# controller.net
KiCad netlist of a schematic drawn in EAGLE
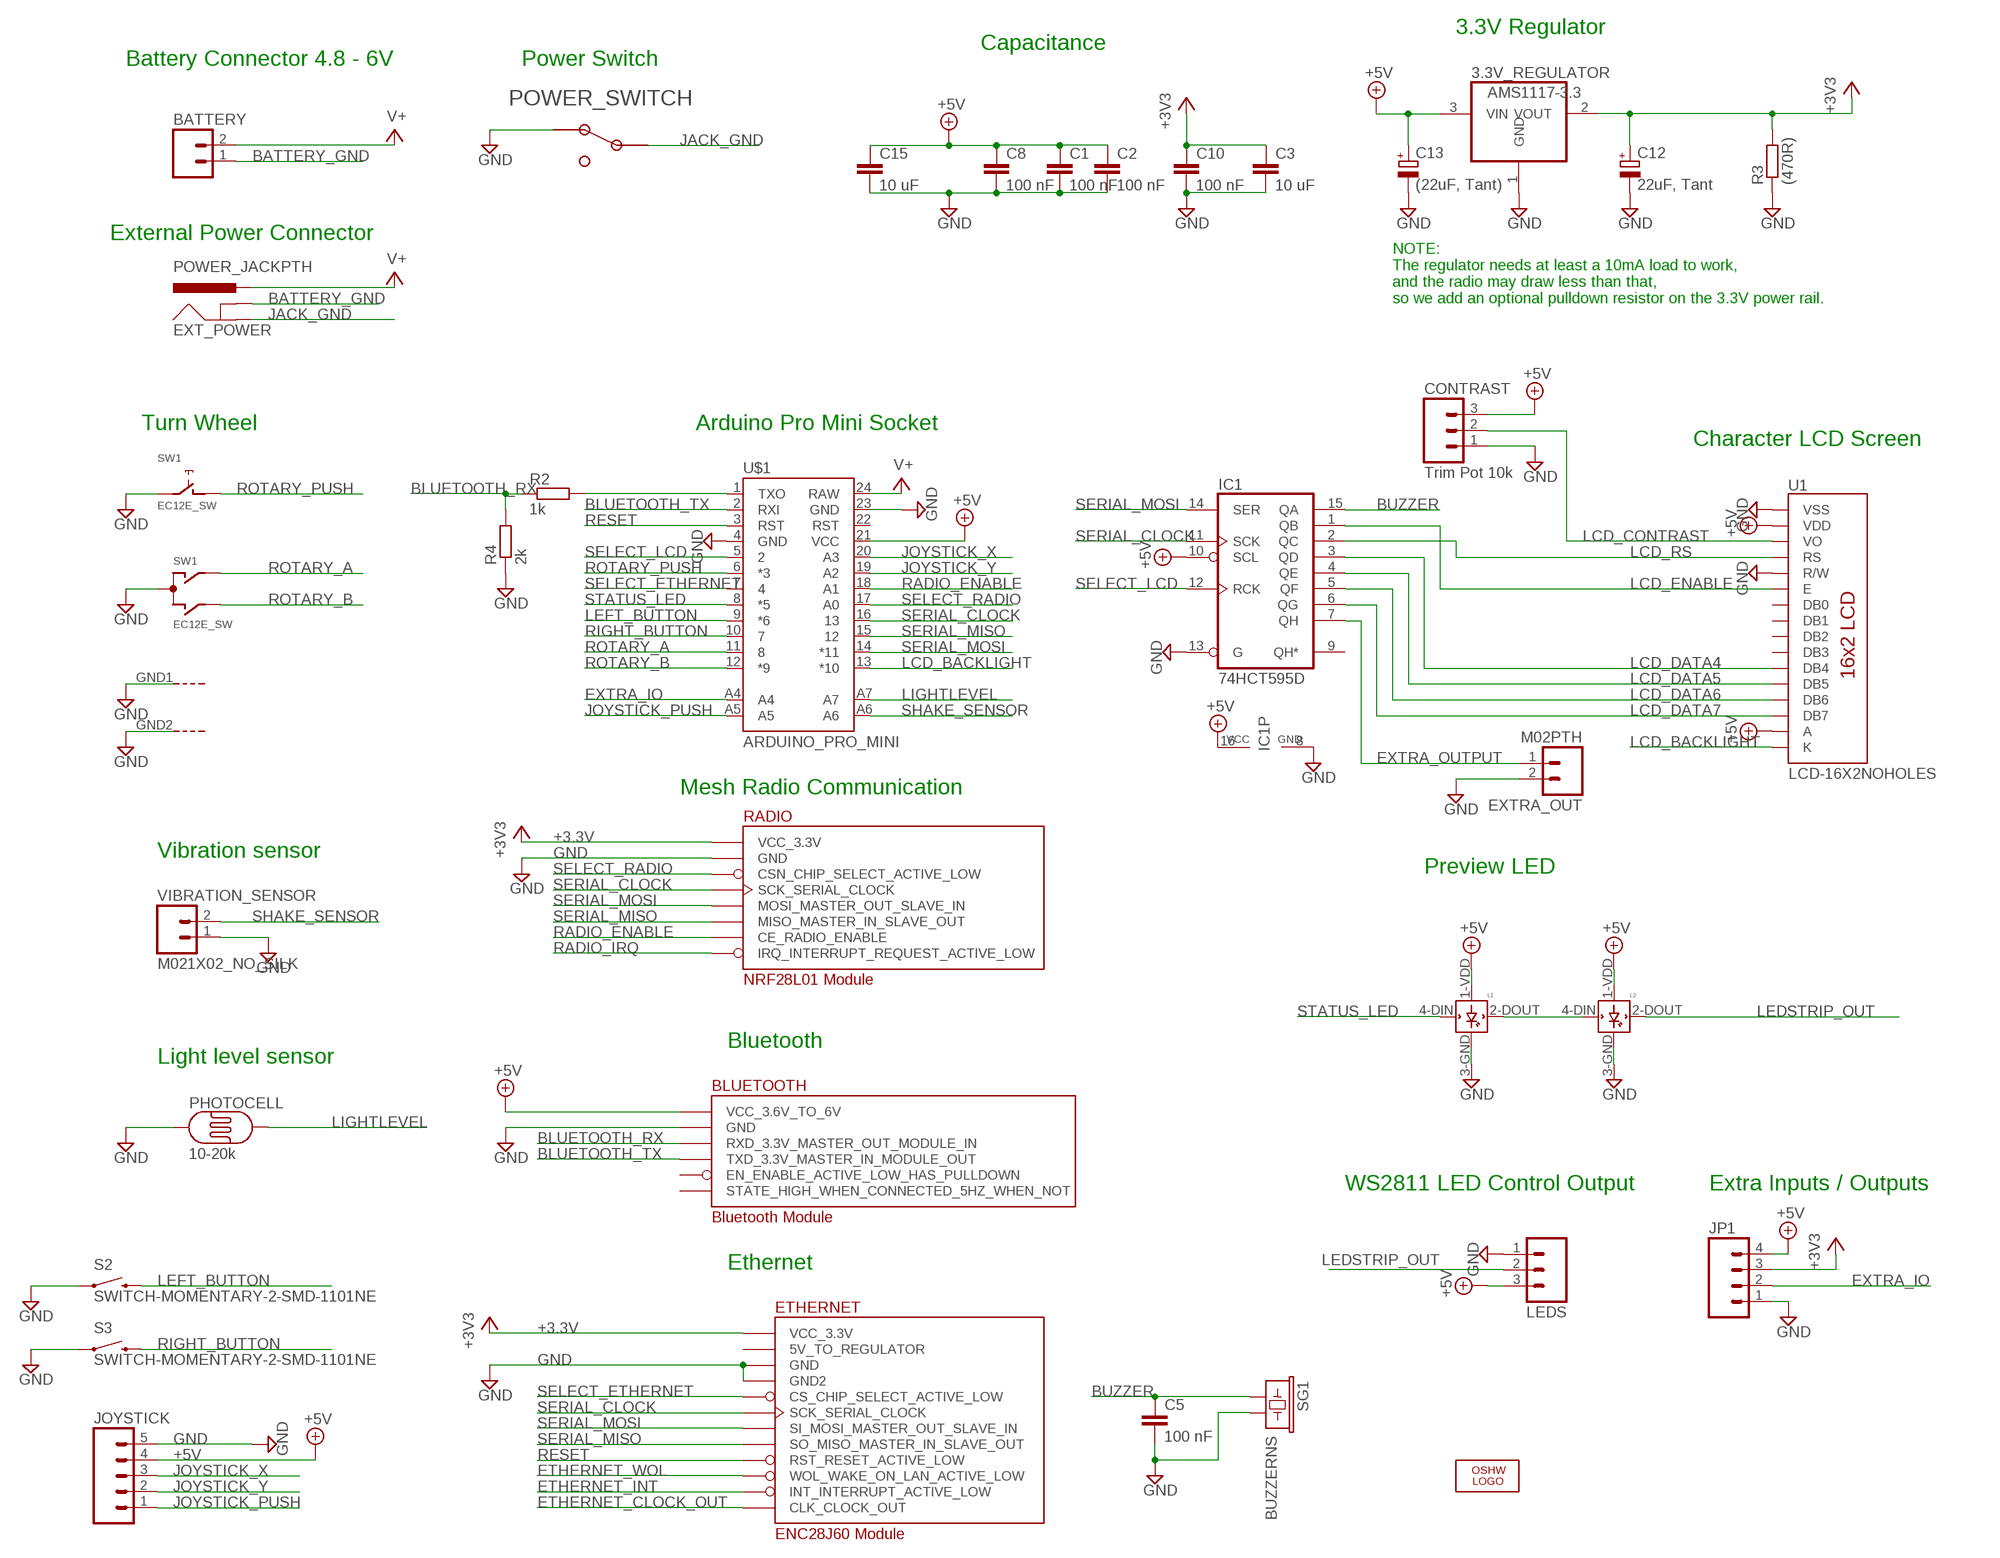
[diagram p0: schematic, sheet 1]

(export (version "E")
  (design (tool "Eeschema 10.0.6"))
  (components
    (comp (ref "3.3V_REGULATOR")
      (value "AMS1117-3.3")
      (footprint "eagle-import:SOT223")
      (fields (field (name "MPN") "REG1117"))
      (libsource (lib "eagle-import") (part "REG1117"))
    )
    (comp (ref "BATTERY")
      (value "M02LOCK_LONGPADS")
      (footprint "eagle-import:1X02_LOCK_LONGPADS")
      (libsource (lib "eagle-import") (part "M02LOCK_LONGPADS"))
    )
    (comp (ref "BLUETOOTH")
      (value "Bluetooth Module")
      (footprint "eagle-import:BLUETOOTH_MODULE")
      (libsource (lib "eagle-import") (part "BLUETOOTH_MODULE"))
    )
    (comp (ref "C1")
      (value "100 nF")
      (footprint "eagle-import:C0805")
      (libsource (lib "eagle-import") (part "C-EUC0805"))
    )
    (comp (ref "C2")
      (value "100 nF")
      (footprint "eagle-import:C0805")
      (libsource (lib "eagle-import") (part "C-EUC0805"))
    )
    (comp (ref "C3")
      (value "10 uF")
      (footprint "eagle-import:C0805K")
      (libsource (lib "eagle-import") (part "C-EUC0805K"))
    )
    (comp (ref "C5")
      (value "100 nF")
      (footprint "eagle-import:C0805")
      (libsource (lib "eagle-import") (part "C-EUC0805"))
    )
    (comp (ref "C8")
      (value "100 nF")
      (footprint "eagle-import:C0805")
      (libsource (lib "eagle-import") (part "C-EUC0805"))
    )
    (comp (ref "C10")
      (value "100 nF")
      (footprint "eagle-import:C0805")
      (libsource (lib "eagle-import") (part "C-EUC0805"))
    )
    (comp (ref "C12")
      (value "22uF, Tant")
      (footprint "eagle-import:SMC_A")
      (libsource (lib "eagle-import") (part "CPOL-EUSMCA"))
    )
    (comp (ref "C13")
      (value "(22uF, Tant)")
      (footprint "eagle-import:SMC_A")
      (libsource (lib "eagle-import") (part "CPOL-EUSMCA"))
    )
    (comp (ref "C15")
      (value "10 uF")
      (footprint "eagle-import:C0805K")
      (libsource (lib "eagle-import") (part "C-EUC0805K"))
    )
    (comp (ref "CONTRAST")
      (value "Trim Pot 10k")
      (footprint "eagle-import:1X03_NO_SILK")
      (libsource (lib "eagle-import") (part "M031X03_NO_SILK"))
    )
    (comp (ref "ETHERNET")
      (value "ENC28J60 Module")
      (footprint "eagle-import:ETHERNET_ENC28J60_MODULE")
      (libsource (lib "eagle-import") (part "ETHERNET_ENC28J60_MODULE"))
    )
    (comp (ref "EXTRA_OUT")
      (value "M02PTH")
      (footprint "eagle-import:1X02")
      (libsource (lib "eagle-import") (part "SparkFun-Connectors_M02PTH"))
    )
    (comp (ref "EXT_POWER")
      (value "POWER_JACKPTH")
      (footprint "eagle-import:POWER_JACK_PTH")
      (libsource (lib "eagle-import") (part "POWER_JACKPTH"))
    )
    (comp (ref "IC1")
      (value "74HCT595D")
      (footprint "eagle-import:SO16")
      (libsource (lib "eagle-import") (part "74595DHCT"))
    )
    (comp (ref "JOYSTICK")
      (value "M05NO_SILK")
      (footprint "eagle-import:1X05_NO_SILK")
      (libsource (lib "eagle-import") (part "M05NO_SILK"))
    )
    (comp (ref "JP1")
      (value "M041X04_NO_SILK")
      (footprint "eagle-import:1X04_NO_SILK")
      (libsource (lib "eagle-import") (part "M041X04_NO_SILK"))
    )
    (comp (ref "L1")
      (value "WS2812B")
      (footprint "eagle-import:WS2812B")
      (libsource (lib "eagle-import") (part "WS2812B"))
    )
    (comp (ref "L2")
      (value "WS2812B")
      (footprint "eagle-import:WS2812B")
      (libsource (lib "eagle-import") (part "WS2812B"))
    )
    (comp (ref "LEDS")
      (value "M03PTH")
      (footprint "eagle-import:1X03")
      (libsource (lib "eagle-import") (part "M03PTH"))
    )
    (comp (ref "LOGO3")
      (value "LOGO-OSHW-8MILX0100-NT")
      (footprint "eagle-import:OSHW_8X100_NOTEXT")
      (libsource (lib "eagle-import") (part "LOGO-OSHW-8MILX0100-NT"))
    )
    (comp (ref "PHOTOCELL")
      (value "10-20k")
      (footprint "eagle-import:PHOTOCELL")
      (libsource (lib "eagle-import") (part "PHOTOCELLPTH"))
    )
    (comp (ref "POWER_SWITCH")
      (value "KNC1-101-2P")
      (footprint "eagle-import:KNC1-101-2P")
      (libsource (lib "eagle-import") (part "KNC1-101-2P"))
    )
    (comp (ref "R2")
      (value "1k")
      (footprint "eagle-import:M0805")
      (libsource (lib "eagle-import") (part "R-EU_M0805"))
    )
    (comp (ref "R3")
      (value "(470R)")
      (footprint "eagle-import:M0805")
      (libsource (lib "eagle-import") (part "R-EU_M0805"))
    )
    (comp (ref "R4")
      (value "2k")
      (footprint "eagle-import:M0805")
      (libsource (lib "eagle-import") (part "R-EU_M0805"))
    )
    (comp (ref "RADIO")
      (value "NRF28L01 Module")
      (footprint "eagle-import:NRF24L01_MODULE")
      (libsource (lib "eagle-import") (part "NRF24L01_MODULE"))
    )
    (comp (ref "S2")
      (value "SWITCH-MOMENTARY-2-SMD-1101NE")
      (footprint "eagle-import:TACTILE-SWITCH-1101NE")
      (libsource (lib "eagle-import") (part "SWITCH-MOMENTARY-2-SMD-1101NE"))
    )
    (comp (ref "S3")
      (value "SWITCH-MOMENTARY-2-SMD-1101NE")
      (footprint "eagle-import:TACTILE-SWITCH-1101NE")
      (libsource (lib "eagle-import") (part "SWITCH-MOMENTARY-2-SMD-1101NE"))
    )
    (comp (ref "SG1")
      (value "BUZZERNS")
      (footprint "eagle-import:BUZZER-12MM-NS")
      (libsource (lib "eagle-import") (part "BUZZERNS"))
    )
    (comp (ref "SW1")
      (value "EC12E_SW")
      (footprint "eagle-import:ALPS_EC12E_SW")
      (fields (field (name "MPN") "EC12E2424407"))
      (libsource (lib "eagle-import") (part "EC12E_SW"))
    )
    (comp (ref "U$1")
      (value "ARDUINO_PRO_MINI")
      (footprint "eagle-import:ARDUINO_PRO_MINI")
      (libsource (lib "eagle-import") (part "ARDUINO_PRO_MINI"))
    )
    (comp (ref "U1")
      (value "LCD-16X2NOHOLES")
      (footprint "eagle-import:LCD-16X2_NOHOLES")
      (libsource (lib "eagle-import") (part "LCD-16X2NOHOLES"))
    )
    (comp (ref "VIBRATION_SENSOR")
      (value "M021X02_NO_SILK")
      (footprint "eagle-import:1X02_NO_SILK")
      (libsource (lib "eagle-import") (part "SparkFun-Connectors_M021X02_NO_SILK"))
    )
  )
  (nets
    (net (code "1") (name "+3V3") (class "Default")
      (node (ref "3.3V_REGULATOR") (pin "2") (pinfunction "VOUT_2") (pintype "output"))
      (node (ref "C10") (pin "1") (pinfunction "1_1") (pintype "passive"))
      (node (ref "C12") (pin "+") (pinfunction "+_+") (pintype "passive"))
      (node (ref "C3") (pin "1") (pinfunction "1_1") (pintype "passive"))
      (node (ref "ETHERNET") (pin "P$2") (pinfunction "VCC_3.3V_P$2") (pintype "power_in"))
      (node (ref "JP1") (pin "3") (pinfunction "3_3") (pintype "passive"))
      (node (ref "R3") (pin "2") (pinfunction "2_2") (pintype "passive"))
      (node (ref "RADIO") (pin "P$2") (pinfunction "VCC_3.3V_P$2") (pintype "power_in"))
    )
    (net (code "2") (name "+5V") (class "Default")
      (node (ref "3.3V_REGULATOR") (pin "3") (pinfunction "VIN_3") (pintype "input"))
      (node (ref "BLUETOOTH") (pin "P$5") (pinfunction "VCC_3.6V_TO_6V_P$5") (pintype "power_in"))
      (node (ref "C1") (pin "1") (pinfunction "1_1") (pintype "passive"))
      (node (ref "C13") (pin "+") (pinfunction "+_+") (pintype "passive"))
      (node (ref "C15") (pin "1") (pinfunction "1_1") (pintype "passive"))
      (node (ref "C2") (pin "1") (pinfunction "1_1") (pintype "passive"))
      (node (ref "C8") (pin "1") (pinfunction "1_1") (pintype "passive"))
      (node (ref "CONTRAST") (pin "3") (pinfunction "3_3") (pintype "passive"))
      (node (ref "IC1") (pin "10") (pinfunction "SCL_10") (pintype "input"))
      (node (ref "IC1") (pin "16") (pinfunction "VCC_16") (pintype "power_in"))
      (node (ref "JOYSTICK") (pin "4") (pinfunction "4_4") (pintype "passive"))
      (node (ref "JP1") (pin "4") (pinfunction "4_4") (pintype "passive"))
      (node (ref "L1") (pin "1-VDD") (pinfunction "VDD_1-VDD") (pintype "bidirectional"))
      (node (ref "L2") (pin "1-VDD") (pinfunction "VDD_1-VDD") (pintype "bidirectional"))
      (node (ref "LEDS") (pin "3") (pinfunction "3_3") (pintype "passive"))
      (node (ref "U$1") (pin "21") (pinfunction "VCC_21") (pintype "bidirectional"))
      (node (ref "U1") (pin "15") (pinfunction "A_15") (pintype "power_in"))
      (node (ref "U1") (pin "2") (pinfunction "VDD_2") (pintype "power_in"))
    )
    (net (code "3") (name "/5V_TO_REGULATOR") (class "Default")
      (node (ref "ETHERNET") (pin "P$12") (pinfunction "5V_TO_REGULATOR_P$12") (pintype "power_in"))
    )
    (net (code "4") (name "/BATTERY_GND") (class "Default")
      (node (ref "BATTERY") (pin "1") (pinfunction "1_1") (pintype "passive"))
      (node (ref "EXT_POWER") (pin "GNDBREAK") (pinfunction "GNDBREAK_GNDBREAK") (pintype "bidirectional"))
    )
    (net (code "5") (name "/BLUETOOTH_RX") (class "Default")
      (node (ref "BLUETOOTH") (pin "P$2") (pinfunction "RXD_3.3V_MASTER_OUT_MODULE_IN_P$2") (pintype "input"))
      (node (ref "R2") (pin "1") (pinfunction "1_1") (pintype "passive"))
      (node (ref "R4") (pin "2") (pinfunction "2_2") (pintype "passive"))
    )
    (net (code "6") (name "/BLUETOOTH_TX") (class "Default")
      (node (ref "BLUETOOTH") (pin "P$3") (pinfunction "TXD_3.3V_MASTER_IN_MODULE_OUT_P$3") (pintype "output"))
      (node (ref "U$1") (pin "2") (pinfunction "RXI_2") (pintype "bidirectional"))
    )
    (net (code "7") (name "/BUZZER") (class "Default")
      (node (ref "C5") (pin "1") (pinfunction "1_1") (pintype "passive"))
      (node (ref "IC1") (pin "15") (pinfunction "QA_15") (pintype "tri_state"))
      (node (ref "SG1") (pin "+") (pinfunction "1_+") (pintype "passive"))
    )
    (net (code "8") (name "/ETHERNET_CLOCK_OUT") (class "Default")
      (node (ref "ETHERNET") (pin "P$9") (pinfunction "CLK_CLOCK_OUT_P$9") (pintype "output"))
    )
    (net (code "9") (name "/ETHERNET_INT") (class "Default")
      (node (ref "ETHERNET") (pin "P$10") (pinfunction "INT_INTERRUPT_ACTIVE_LOW_P$10") (pintype "output"))
    )
    (net (code "10") (name "/ETHERNET_WOL") (class "Default")
      (node (ref "ETHERNET") (pin "P$7") (pinfunction "WOL_WAKE_ON_LAN_ACTIVE_LOW_P$7") (pintype "output"))
    )
    (net (code "11") (name "/EXTRA_IO") (class "Default")
      (node (ref "JP1") (pin "2") (pinfunction "2_2") (pintype "passive"))
      (node (ref "U$1") (pin "A4") (pinfunction "A4_A4") (pintype "bidirectional"))
    )
    (net (code "12") (name "/EXTRA_OUTPUT") (class "Default")
      (node (ref "EXTRA_OUT") (pin "1") (pinfunction "1_1") (pintype "passive"))
      (node (ref "IC1") (pin "7") (pinfunction "QH_7") (pintype "tri_state"))
    )
    (net (code "13") (name "/JACK_GND") (class "Default")
      (node (ref "EXT_POWER") (pin "GND") (pinfunction "GND_GND") (pintype "bidirectional"))
      (node (ref "POWER_SWITCH") (pin "P$2") (pinfunction "P$2_P$2") (pintype "bidirectional"))
    )
    (net (code "14") (name "/JOYSTICK_PUSH") (class "Default")
      (node (ref "JOYSTICK") (pin "1") (pinfunction "1_1") (pintype "passive"))
      (node (ref "U$1") (pin "A5") (pinfunction "A5_A5") (pintype "bidirectional"))
    )
    (net (code "15") (name "/JOYSTICK_X") (class "Default")
      (node (ref "JOYSTICK") (pin "3") (pinfunction "3_3") (pintype "passive"))
      (node (ref "U$1") (pin "20") (pinfunction "A3_20") (pintype "bidirectional"))
    )
    (net (code "16") (name "/JOYSTICK_Y") (class "Default")
      (node (ref "JOYSTICK") (pin "2") (pinfunction "2_2") (pintype "passive"))
      (node (ref "U$1") (pin "19") (pinfunction "A2_19") (pintype "bidirectional"))
    )
    (net (code "17") (name "/LCD_BACKLIGHT") (class "Default")
      (node (ref "U$1") (pin "13") (pinfunction "*10_13") (pintype "bidirectional"))
      (node (ref "U1") (pin "16") (pinfunction "K_16") (pintype "power_in"))
    )
    (net (code "18") (name "/LCD_CONTRAST") (class "Default")
      (node (ref "CONTRAST") (pin "2") (pinfunction "2_2") (pintype "passive"))
      (node (ref "U1") (pin "3") (pinfunction "VO_3") (pintype "bidirectional"))
    )
    (net (code "19") (name "/LCD_DATA4") (class "Default")
      (node (ref "IC1") (pin "3") (pinfunction "QD_3") (pintype "tri_state"))
      (node (ref "U1") (pin "11") (pinfunction "DB4_11") (pintype "bidirectional"))
    )
    (net (code "20") (name "/LCD_DATA5") (class "Default")
      (node (ref "IC1") (pin "4") (pinfunction "QE_4") (pintype "tri_state"))
      (node (ref "U1") (pin "12") (pinfunction "DB5_12") (pintype "bidirectional"))
    )
    (net (code "21") (name "/LCD_DATA6") (class "Default")
      (node (ref "IC1") (pin "5") (pinfunction "QF_5") (pintype "tri_state"))
      (node (ref "U1") (pin "13") (pinfunction "DB6_13") (pintype "bidirectional"))
    )
    (net (code "22") (name "/LCD_DATA7") (class "Default")
      (node (ref "IC1") (pin "6") (pinfunction "QG_6") (pintype "tri_state"))
      (node (ref "U1") (pin "14") (pinfunction "DB7_14") (pintype "bidirectional"))
    )
    (net (code "23") (name "/LCD_ENABLE") (class "Default")
      (node (ref "IC1") (pin "1") (pinfunction "QB_1") (pintype "tri_state"))
      (node (ref "U1") (pin "6") (pinfunction "E_6") (pintype "input"))
    )
    (net (code "24") (name "/LCD_RS") (class "Default")
      (node (ref "IC1") (pin "2") (pinfunction "QC_2") (pintype "tri_state"))
      (node (ref "U1") (pin "4") (pinfunction "RS_4") (pintype "input"))
    )
    (net (code "25") (name "/LEDSTRIP_OUT") (class "Default")
      (node (ref "L2") (pin "2-DOUT") (pinfunction "DOUT_2-DOUT") (pintype "output"))
      (node (ref "LEDS") (pin "2") (pinfunction "2_2") (pintype "passive"))
    )
    (net (code "26") (name "/LEFT_BUTTON") (class "Default")
      (node (ref "S2") (pin "P$2") (pinfunction "2_P$2") (pintype "passive"))
      (node (ref "U$1") (pin "9") (pinfunction "*6_9") (pintype "bidirectional"))
    )
    (net (code "27") (name "/LIGHTLEVEL") (class "Default")
      (node (ref "PHOTOCELL") (pin "2") (pinfunction "P$2_2") (pintype "bidirectional"))
      (node (ref "U$1") (pin "A7") (pinfunction "A7_A7") (pintype "bidirectional"))
    )
    (net (code "28") (name "/RADIO_ENABLE") (class "Default")
      (node (ref "RADIO") (pin "P$3") (pinfunction "CE_RADIO_ENABLE_P$3") (pintype "input"))
      (node (ref "U$1") (pin "18") (pinfunction "A1_18") (pintype "bidirectional"))
    )
    (net (code "29") (name "/RADIO_IRQ") (class "Default")
      (node (ref "RADIO") (pin "P$8") (pinfunction "IRQ_INTERRUPT_REQUEST_ACTIVE_LOW_P$8") (pintype "output"))
    )
    (net (code "30") (name "/RESET") (class "Default")
      (node (ref "ETHERNET") (pin "P$4") (pinfunction "RST_RESET_ACTIVE_LOW_P$4") (pintype "input"))
      (node (ref "U$1") (pin "3") (pinfunction "RST_3") (pintype "bidirectional"))
    )
    (net (code "31") (name "/RIGHT_BUTTON") (class "Default")
      (node (ref "S3") (pin "P$2") (pinfunction "2_P$2") (pintype "passive"))
      (node (ref "U$1") (pin "10") (pinfunction "7_10") (pintype "bidirectional"))
    )
    (net (code "32") (name "/ROTARY_A") (class "Default")
      (node (ref "SW1") (pin "A") (pinfunction "A_A") (pintype "passive"))
      (node (ref "U$1") (pin "11") (pinfunction "8_11") (pintype "bidirectional"))
    )
    (net (code "33") (name "/ROTARY_B") (class "Default")
      (node (ref "SW1") (pin "B") (pinfunction "B_B") (pintype "passive"))
      (node (ref "U$1") (pin "12") (pinfunction "*9_12") (pintype "bidirectional"))
    )
    (net (code "34") (name "/ROTARY_PUSH") (class "Default")
      (node (ref "SW1") (pin "D") (pinfunction "1_D") (pintype "passive"))
      (node (ref "U$1") (pin "6") (pinfunction "*3_6") (pintype "bidirectional"))
    )
    (net (code "35") (name "/SELECT_ETHERNET") (class "Default")
      (node (ref "ETHERNET") (pin "P$3") (pinfunction "CS_CHIP_SELECT_ACTIVE_LOW_P$3") (pintype "input"))
      (node (ref "U$1") (pin "7") (pinfunction "4_7") (pintype "bidirectional"))
    )
    (net (code "36") (name "/SELECT_LCD") (class "Default")
      (node (ref "IC1") (pin "12") (pinfunction "RCK_12") (pintype "input"))
      (node (ref "U$1") (pin "5") (pinfunction "2_5") (pintype "bidirectional"))
    )
    (net (code "37") (name "/SELECT_RADIO") (class "Default")
      (node (ref "RADIO") (pin "P$4") (pinfunction "CSN_CHIP_SELECT_ACTIVE_LOW_P$4") (pintype "input"))
      (node (ref "U$1") (pin "17") (pinfunction "A0_17") (pintype "bidirectional"))
    )
    (net (code "38") (name "/SERIAL_CLOCK") (class "Default")
      (node (ref "ETHERNET") (pin "P$6") (pinfunction "SCK_SERIAL_CLOCK_P$6") (pintype "input"))
      (node (ref "IC1") (pin "11") (pinfunction "SCK_11") (pintype "input"))
      (node (ref "RADIO") (pin "P$5") (pinfunction "SCK_SERIAL_CLOCK_P$5") (pintype "input"))
      (node (ref "U$1") (pin "16") (pinfunction "13_16") (pintype "bidirectional"))
    )
    (net (code "39") (name "/SERIAL_MISO") (class "Default")
      (node (ref "ETHERNET") (pin "P$8") (pinfunction "SO_MISO_MASTER_IN_SLAVE_OUT_P$8") (pintype "output"))
      (node (ref "RADIO") (pin "P$7") (pinfunction "MISO_MASTER_IN_SLAVE_OUT_P$7") (pintype "output"))
      (node (ref "U$1") (pin "15") (pinfunction "12_15") (pintype "bidirectional"))
    )
    (net (code "40") (name "/SERIAL_MOSI") (class "Default")
      (node (ref "ETHERNET") (pin "P$5") (pinfunction "SI_MOSI_MASTER_OUT_SLAVE_IN_P$5") (pintype "input"))
      (node (ref "IC1") (pin "14") (pinfunction "SER_14") (pintype "input"))
      (node (ref "RADIO") (pin "P$6") (pinfunction "MOSI_MASTER_OUT_SLAVE_IN_P$6") (pintype "input"))
      (node (ref "U$1") (pin "14") (pinfunction "*11_14") (pintype "bidirectional"))
    )
    (net (code "41") (name "/SHAKE_SENSOR") (class "Default")
      (node (ref "U$1") (pin "A6") (pinfunction "A6_A6") (pintype "bidirectional"))
      (node (ref "VIBRATION_SENSOR") (pin "2") (pinfunction "2_2") (pintype "passive"))
    )
    (net (code "42") (name "/STATUS_LED") (class "Default")
      (node (ref "L1") (pin "4-DIN") (pinfunction "DIN_4-DIN") (pintype "input"))
      (node (ref "U$1") (pin "8") (pinfunction "*5_8") (pintype "bidirectional"))
    )
    (net (code "43") (name "GND") (class "Default")
      (node (ref "3.3V_REGULATOR") (pin "1") (pinfunction "GND_1") (pintype "power_in"))
      (node (ref "BLUETOOTH") (pin "P$4") (pinfunction "GND_P$4") (pintype "power_in"))
      (node (ref "C1") (pin "2") (pinfunction "2_2") (pintype "passive"))
      (node (ref "C10") (pin "2") (pinfunction "2_2") (pintype "passive"))
      (node (ref "C12") (pin "-") (pinfunction "-_-") (pintype "passive"))
      (node (ref "C13") (pin "-") (pinfunction "-_-") (pintype "passive"))
      (node (ref "C15") (pin "2") (pinfunction "2_2") (pintype "passive"))
      (node (ref "C2") (pin "2") (pinfunction "2_2") (pintype "passive"))
      (node (ref "C3") (pin "2") (pinfunction "2_2") (pintype "passive"))
      (node (ref "C5") (pin "2") (pinfunction "2_2") (pintype "passive"))
      (node (ref "C8") (pin "2") (pinfunction "2_2") (pintype "passive"))
      (node (ref "CONTRAST") (pin "1") (pinfunction "1_1") (pintype "passive"))
      (node (ref "ETHERNET") (pin "P$1") (pinfunction "GND_P$1") (pintype "power_in"))
      (node (ref "ETHERNET") (pin "P$11") (pinfunction "GND2_P$11") (pintype "power_in"))
      (node (ref "EXTRA_OUT") (pin "2") (pinfunction "2_2") (pintype "passive"))
      (node (ref "IC1") (pin "13") (pinfunction "G_13") (pintype "input"))
      (node (ref "IC1") (pin "8") (pinfunction "GND_8") (pintype "power_in"))
      (node (ref "JOYSTICK") (pin "5") (pinfunction "5_5") (pintype "passive"))
      (node (ref "JP1") (pin "1") (pinfunction "1_1") (pintype "passive"))
      (node (ref "L1") (pin "3-GND") (pinfunction "GND_3-GND") (pintype "bidirectional"))
      (node (ref "L2") (pin "3-GND") (pinfunction "GND_3-GND") (pintype "bidirectional"))
      (node (ref "LEDS") (pin "1") (pinfunction "1_1") (pintype "passive"))
      (node (ref "PHOTOCELL") (pin "1") (pinfunction "P$1_1") (pintype "bidirectional"))
      (node (ref "POWER_SWITCH") (pin "P$1") (pinfunction "P$1_P$1") (pintype "bidirectional"))
      (node (ref "R3") (pin "1") (pinfunction "1_1") (pintype "passive"))
      (node (ref "R4") (pin "1") (pinfunction "1_1") (pintype "passive"))
      (node (ref "RADIO") (pin "P$1") (pinfunction "GND_P$1") (pintype "power_in"))
      (node (ref "S2") (pin "P$1") (pinfunction "1_P$1") (pintype "passive"))
      (node (ref "S3") (pin "P$1") (pinfunction "1_P$1") (pintype "passive"))
      (node (ref "SG1") (pin "-") (pinfunction "2_-") (pintype "passive"))
      (node (ref "SW1") (pin "C") (pinfunction "C_C") (pintype "passive"))
      (node (ref "SW1") (pin "E") (pinfunction "2_E") (pintype "passive"))
      (node (ref "SW1") (pin "GND1") (pinfunction "G_GND1") (pintype "passive"))
      (node (ref "SW1") (pin "GND2") (pinfunction "G_GND2") (pintype "passive"))
      (node (ref "U$1") (pin "23") (pinfunction "GND_23") (pintype "bidirectional"))
      (node (ref "U$1") (pin "4") (pinfunction "GND_4") (pintype "bidirectional"))
      (node (ref "U1") (pin "1") (pinfunction "VSS_1") (pintype "power_in"))
      (node (ref "U1") (pin "5") (pinfunction "R/W_5") (pintype "input"))
      (node (ref "VIBRATION_SENSOR") (pin "1") (pinfunction "1_1") (pintype "passive"))
    )
    (net (code "44") (name "Net-(L1-DOUT)") (class "Default")
      (node (ref "L1") (pin "2-DOUT") (pinfunction "DOUT_2-DOUT") (pintype "output"))
      (node (ref "L2") (pin "4-DIN") (pinfunction "DIN_4-DIN") (pintype "input"))
    )
    (net (code "45") (name "Net-(U$1-TXO)") (class "Default")
      (node (ref "R2") (pin "2") (pinfunction "2_2") (pintype "passive"))
      (node (ref "U$1") (pin "1") (pinfunction "TXO_1") (pintype "bidirectional"))
    )
    (net (code "46") (name "V+") (class "Default")
      (node (ref "BATTERY") (pin "2") (pinfunction "2_2") (pintype "passive"))
      (node (ref "EXT_POWER") (pin "PWR") (pinfunction "PWR_PWR") (pintype "bidirectional"))
      (node (ref "U$1") (pin "24") (pinfunction "RAW_24") (pintype "bidirectional"))
    )
    (net (code "47") (name "unconnected-(BLUETOOTH-EN_ENABLE_ACTIVE_LOW_HAS_PULLDOWN-PadP$6)") (class "Default")
      (node (ref "BLUETOOTH") (pin "P$6") (pinfunction "EN_ENABLE_ACTIVE_LOW_HAS_PULLDOWN_P$6") (pintype "input"))
    )
    (net (code "48") (name "unconnected-(BLUETOOTH-STATE_HIGH_WHEN_CONNECTED_5HZ_WHEN_NOT-PadP$1)") (class "Default")
      (node (ref "BLUETOOTH") (pin "P$1") (pinfunction "STATE_HIGH_WHEN_CONNECTED_5HZ_WHEN_NOT_P$1") (pintype "output"))
    )
    (net (code "49") (name "unconnected-(IC1A-QH*-Pad9)") (class "Default")
      (node (ref "IC1") (pin "9") (pinfunction "QH*_9") (pintype "tri_state"))
    )
    (net (code "50") (name "unconnected-(U$1-RST-Pad22)") (class "Default")
      (node (ref "U$1") (pin "22") (pinfunction "RST_22") (pintype "bidirectional"))
    )
    (net (code "51") (name "unconnected-(U1-DB0-Pad7)") (class "Default")
      (node (ref "U1") (pin "7") (pinfunction "DB0_7") (pintype "bidirectional"))
    )
    (net (code "52") (name "unconnected-(U1-DB1-Pad8)") (class "Default")
      (node (ref "U1") (pin "8") (pinfunction "DB1_8") (pintype "bidirectional"))
    )
    (net (code "53") (name "unconnected-(U1-DB2-Pad9)") (class "Default")
      (node (ref "U1") (pin "9") (pinfunction "DB2_9") (pintype "bidirectional"))
    )
    (net (code "54") (name "unconnected-(U1-DB3-Pad10)") (class "Default")
      (node (ref "U1") (pin "10") (pinfunction "DB3_10") (pintype "bidirectional"))
    )
  )
)
